# Board.net
KiCad netlist of a schematic drawn in EAGLE
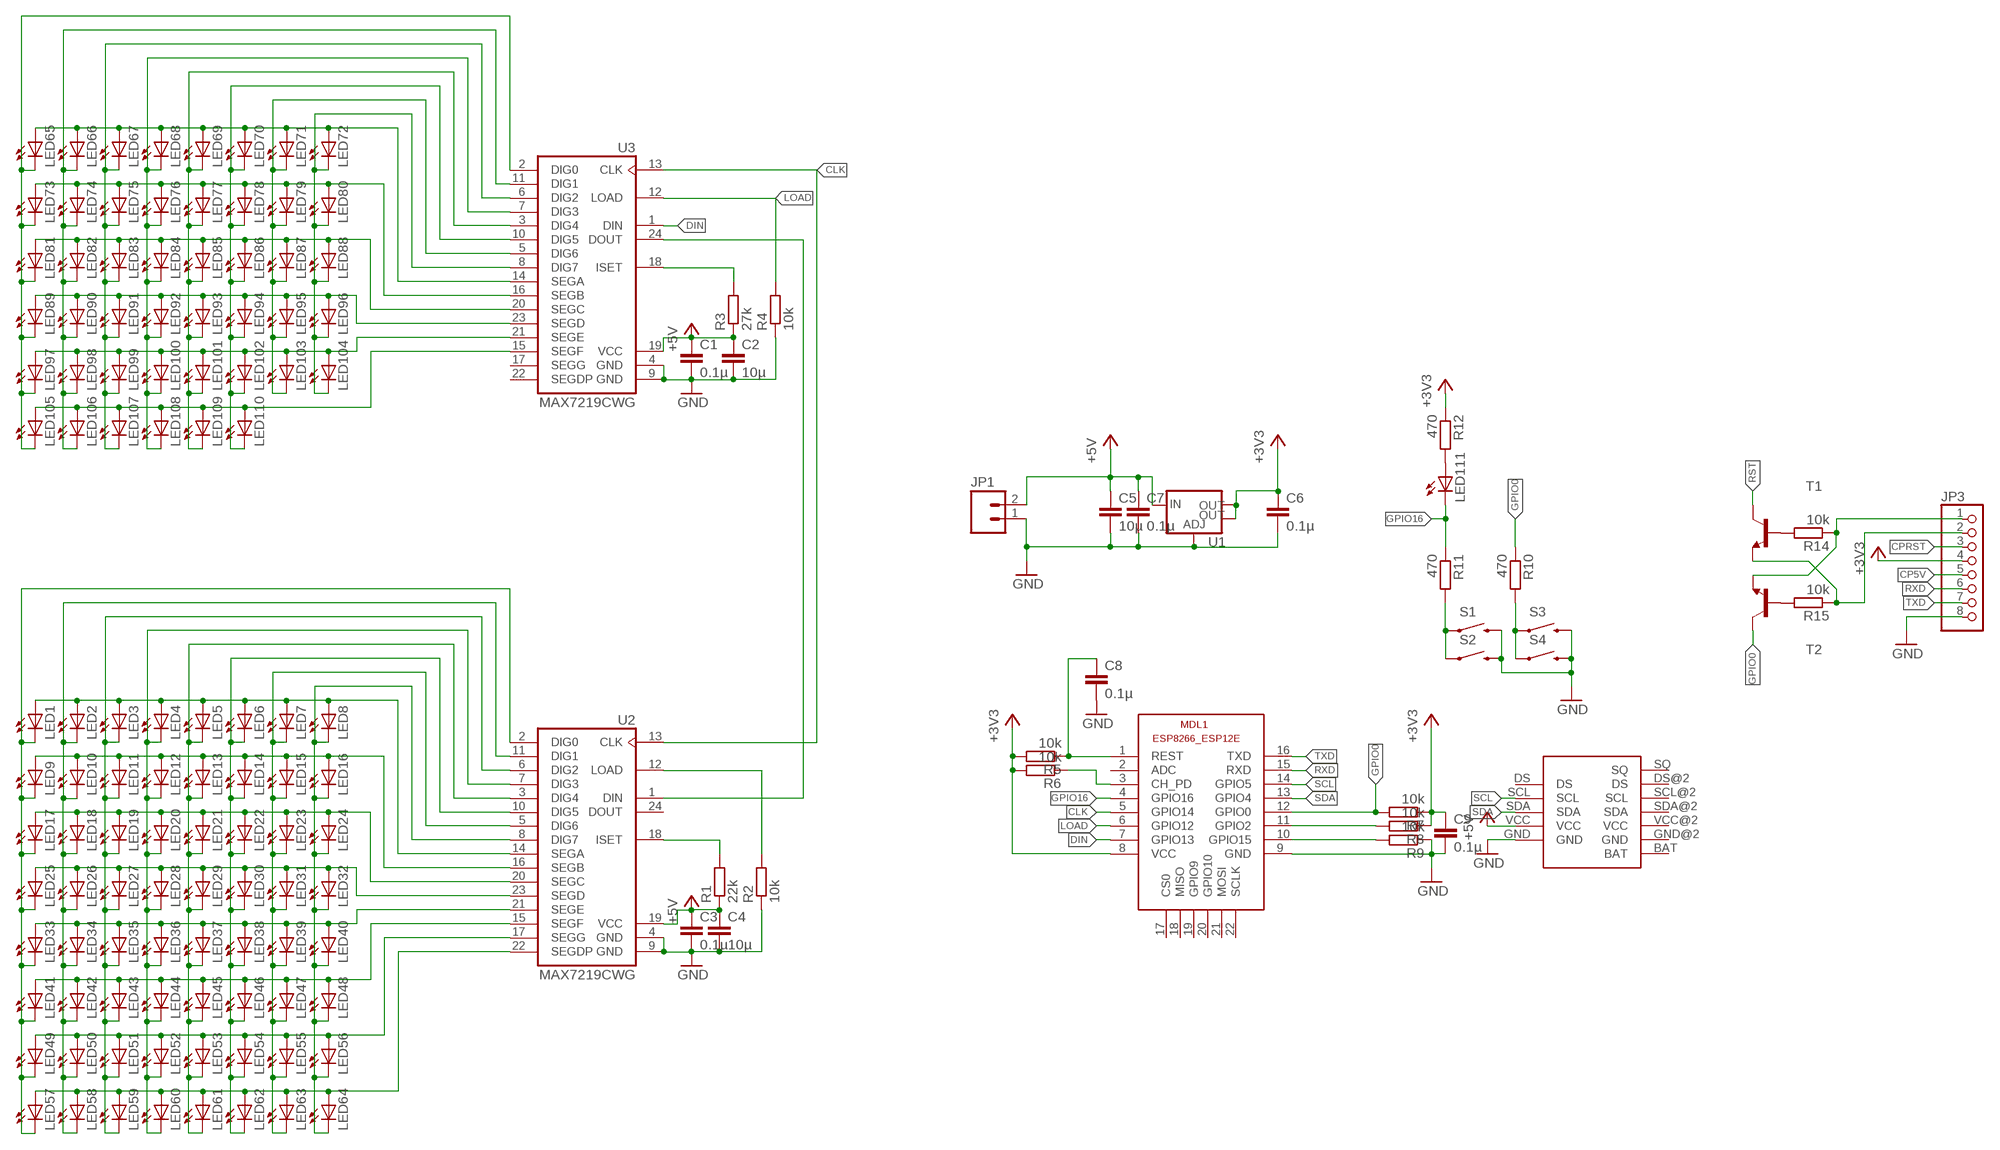
[diagram p0: schematic, sheet 1]

(export (version "E")
  (design (tool "Eeschema 10.0.6"))
  (components
    (comp (ref "C1")
      (value "0.1µ")
      (footprint "eagle-import:C0603")
      (libsource (lib "eagle-import") (part "C-EUC0603"))
    )
    (comp (ref "C2")
      (value "10µ")
      (footprint "eagle-import:C0603")
      (libsource (lib "eagle-import") (part "C-EUC0603"))
    )
    (comp (ref "C3")
      (value "0.1µ")
      (footprint "eagle-import:C0603")
      (libsource (lib "eagle-import") (part "C-EUC0603"))
    )
    (comp (ref "C4")
      (value "10µ")
      (footprint "eagle-import:C0603")
      (libsource (lib "eagle-import") (part "C-EUC0603"))
    )
    (comp (ref "C5")
      (value "10µ")
      (footprint "eagle-import:C0603")
      (libsource (lib "eagle-import") (part "C-EUC0603"))
    )
    (comp (ref "C6")
      (value "0.1µ")
      (footprint "eagle-import:C0603")
      (libsource (lib "eagle-import") (part "C-EUC0603"))
    )
    (comp (ref "C7")
      (value "0.1µ")
      (footprint "eagle-import:C0603")
      (libsource (lib "eagle-import") (part "C-EUC0603"))
    )
    (comp (ref "C8")
      (value "0.1µ")
      (footprint "eagle-import:C0603")
      (libsource (lib "eagle-import") (part "C-EUC0603"))
    )
    (comp (ref "C9")
      (value "0.1µ")
      (footprint "eagle-import:C0603")
      (libsource (lib "eagle-import") (part "C-EUC0603"))
    )
    (comp (ref "JP1")
      (value "M02POLAR")
      (footprint "eagle-import:MOLEX-1X2")
      (libsource (lib "eagle-import") (part "M02POLAR"))
    )
    (comp (ref "JP3")
      (value "PINHD-1X8")
      (footprint "eagle-import:1X08")
      (libsource (lib "eagle-import") (part "PINHD-1X8"))
    )
    (comp (ref "LED1")
      (value "LEDCHIPLED_0805")
      (footprint "eagle-import:CHIPLED_0805")
      (libsource (lib "eagle-import") (part "LEDCHIPLED_0805"))
    )
    (comp (ref "LED2")
      (value "LEDCHIPLED_0805")
      (footprint "eagle-import:CHIPLED_0805")
      (libsource (lib "eagle-import") (part "LEDCHIPLED_0805"))
    )
    (comp (ref "LED3")
      (value "LEDCHIPLED_0805")
      (footprint "eagle-import:CHIPLED_0805")
      (libsource (lib "eagle-import") (part "LEDCHIPLED_0805"))
    )
    (comp (ref "LED4")
      (value "LEDCHIPLED_0805")
      (footprint "eagle-import:CHIPLED_0805")
      (libsource (lib "eagle-import") (part "LEDCHIPLED_0805"))
    )
    (comp (ref "LED5")
      (value "LEDCHIPLED_0805")
      (footprint "eagle-import:CHIPLED_0805")
      (libsource (lib "eagle-import") (part "LEDCHIPLED_0805"))
    )
    (comp (ref "LED6")
      (value "LEDCHIPLED_0805")
      (footprint "eagle-import:CHIPLED_0805")
      (libsource (lib "eagle-import") (part "LEDCHIPLED_0805"))
    )
    (comp (ref "LED7")
      (value "LEDCHIPLED_0805")
      (footprint "eagle-import:CHIPLED_0805")
      (libsource (lib "eagle-import") (part "LEDCHIPLED_0805"))
    )
    (comp (ref "LED8")
      (value "LEDCHIPLED_0805")
      (footprint "eagle-import:CHIPLED_0805")
      (libsource (lib "eagle-import") (part "LEDCHIPLED_0805"))
    )
    (comp (ref "LED9")
      (value "LEDCHIPLED_0805")
      (footprint "eagle-import:CHIPLED_0805")
      (libsource (lib "eagle-import") (part "LEDCHIPLED_0805"))
    )
    (comp (ref "LED10")
      (value "LEDCHIPLED_0805")
      (footprint "eagle-import:CHIPLED_0805")
      (libsource (lib "eagle-import") (part "LEDCHIPLED_0805"))
    )
    (comp (ref "LED11")
      (value "LEDCHIPLED_0805")
      (footprint "eagle-import:CHIPLED_0805")
      (libsource (lib "eagle-import") (part "LEDCHIPLED_0805"))
    )
    (comp (ref "LED12")
      (value "LEDCHIPLED_0805")
      (footprint "eagle-import:CHIPLED_0805")
      (libsource (lib "eagle-import") (part "LEDCHIPLED_0805"))
    )
    (comp (ref "LED13")
      (value "LEDCHIPLED_0805")
      (footprint "eagle-import:CHIPLED_0805")
      (libsource (lib "eagle-import") (part "LEDCHIPLED_0805"))
    )
    (comp (ref "LED14")
      (value "LEDCHIPLED_0805")
      (footprint "eagle-import:CHIPLED_0805")
      (libsource (lib "eagle-import") (part "LEDCHIPLED_0805"))
    )
    (comp (ref "LED15")
      (value "LEDCHIPLED_0805")
      (footprint "eagle-import:CHIPLED_0805")
      (libsource (lib "eagle-import") (part "LEDCHIPLED_0805"))
    )
    (comp (ref "LED16")
      (value "LEDCHIPLED_0805")
      (footprint "eagle-import:CHIPLED_0805")
      (libsource (lib "eagle-import") (part "LEDCHIPLED_0805"))
    )
    (comp (ref "LED17")
      (value "LEDCHIPLED_0805")
      (footprint "eagle-import:CHIPLED_0805")
      (libsource (lib "eagle-import") (part "LEDCHIPLED_0805"))
    )
    (comp (ref "LED18")
      (value "LEDCHIPLED_0805")
      (footprint "eagle-import:CHIPLED_0805")
      (libsource (lib "eagle-import") (part "LEDCHIPLED_0805"))
    )
    (comp (ref "LED19")
      (value "LEDCHIPLED_0805")
      (footprint "eagle-import:CHIPLED_0805")
      (libsource (lib "eagle-import") (part "LEDCHIPLED_0805"))
    )
    (comp (ref "LED20")
      (value "LEDCHIPLED_0805")
      (footprint "eagle-import:CHIPLED_0805")
      (libsource (lib "eagle-import") (part "LEDCHIPLED_0805"))
    )
    (comp (ref "LED21")
      (value "LEDCHIPLED_0805")
      (footprint "eagle-import:CHIPLED_0805")
      (libsource (lib "eagle-import") (part "LEDCHIPLED_0805"))
    )
    (comp (ref "LED22")
      (value "LEDCHIPLED_0805")
      (footprint "eagle-import:CHIPLED_0805")
      (libsource (lib "eagle-import") (part "LEDCHIPLED_0805"))
    )
    (comp (ref "LED23")
      (value "LEDCHIPLED_0805")
      (footprint "eagle-import:CHIPLED_0805")
      (libsource (lib "eagle-import") (part "LEDCHIPLED_0805"))
    )
    (comp (ref "LED24")
      (value "LEDCHIPLED_0805")
      (footprint "eagle-import:CHIPLED_0805")
      (libsource (lib "eagle-import") (part "LEDCHIPLED_0805"))
    )
    (comp (ref "LED25")
      (value "LEDCHIPLED_0805")
      (footprint "eagle-import:CHIPLED_0805")
      (libsource (lib "eagle-import") (part "LEDCHIPLED_0805"))
    )
    (comp (ref "LED26")
      (value "LEDCHIPLED_0805")
      (footprint "eagle-import:CHIPLED_0805")
      (libsource (lib "eagle-import") (part "LEDCHIPLED_0805"))
    )
    (comp (ref "LED27")
      (value "LEDCHIPLED_0805")
      (footprint "eagle-import:CHIPLED_0805")
      (libsource (lib "eagle-import") (part "LEDCHIPLED_0805"))
    )
    (comp (ref "LED28")
      (value "LEDCHIPLED_0805")
      (footprint "eagle-import:CHIPLED_0805")
      (libsource (lib "eagle-import") (part "LEDCHIPLED_0805"))
    )
    (comp (ref "LED29")
      (value "LEDCHIPLED_0805")
      (footprint "eagle-import:CHIPLED_0805")
      (libsource (lib "eagle-import") (part "LEDCHIPLED_0805"))
    )
    (comp (ref "LED30")
      (value "LEDCHIPLED_0805")
      (footprint "eagle-import:CHIPLED_0805")
      (libsource (lib "eagle-import") (part "LEDCHIPLED_0805"))
    )
    (comp (ref "LED31")
      (value "LEDCHIPLED_0805")
      (footprint "eagle-import:CHIPLED_0805")
      (libsource (lib "eagle-import") (part "LEDCHIPLED_0805"))
    )
    (comp (ref "LED32")
      (value "LEDCHIPLED_0805")
      (footprint "eagle-import:CHIPLED_0805")
      (libsource (lib "eagle-import") (part "LEDCHIPLED_0805"))
    )
    (comp (ref "LED33")
      (value "LEDCHIPLED_0805")
      (footprint "eagle-import:CHIPLED_0805")
      (libsource (lib "eagle-import") (part "LEDCHIPLED_0805"))
    )
    (comp (ref "LED34")
      (value "LEDCHIPLED_0805")
      (footprint "eagle-import:CHIPLED_0805")
      (libsource (lib "eagle-import") (part "LEDCHIPLED_0805"))
    )
    (comp (ref "LED35")
      (value "LEDCHIPLED_0805")
      (footprint "eagle-import:CHIPLED_0805")
      (libsource (lib "eagle-import") (part "LEDCHIPLED_0805"))
    )
    (comp (ref "LED36")
      (value "LEDCHIPLED_0805")
      (footprint "eagle-import:CHIPLED_0805")
      (libsource (lib "eagle-import") (part "LEDCHIPLED_0805"))
    )
    (comp (ref "LED37")
      (value "LEDCHIPLED_0805")
      (footprint "eagle-import:CHIPLED_0805")
      (libsource (lib "eagle-import") (part "LEDCHIPLED_0805"))
    )
    (comp (ref "LED38")
      (value "LEDCHIPLED_0805")
      (footprint "eagle-import:CHIPLED_0805")
      (libsource (lib "eagle-import") (part "LEDCHIPLED_0805"))
    )
    (comp (ref "LED39")
      (value "LEDCHIPLED_0805")
      (footprint "eagle-import:CHIPLED_0805")
      (libsource (lib "eagle-import") (part "LEDCHIPLED_0805"))
    )
    (comp (ref "LED40")
      (value "LEDCHIPLED_0805")
      (footprint "eagle-import:CHIPLED_0805")
      (libsource (lib "eagle-import") (part "LEDCHIPLED_0805"))
    )
    (comp (ref "LED41")
      (value "LEDCHIPLED_0805")
      (footprint "eagle-import:CHIPLED_0805")
      (libsource (lib "eagle-import") (part "LEDCHIPLED_0805"))
    )
    (comp (ref "LED42")
      (value "LEDCHIPLED_0805")
      (footprint "eagle-import:CHIPLED_0805")
      (libsource (lib "eagle-import") (part "LEDCHIPLED_0805"))
    )
    (comp (ref "LED43")
      (value "LEDCHIPLED_0805")
      (footprint "eagle-import:CHIPLED_0805")
      (libsource (lib "eagle-import") (part "LEDCHIPLED_0805"))
    )
    (comp (ref "LED44")
      (value "LEDCHIPLED_0805")
      (footprint "eagle-import:CHIPLED_0805")
      (libsource (lib "eagle-import") (part "LEDCHIPLED_0805"))
    )
    (comp (ref "LED45")
      (value "LEDCHIPLED_0805")
      (footprint "eagle-import:CHIPLED_0805")
      (libsource (lib "eagle-import") (part "LEDCHIPLED_0805"))
    )
    (comp (ref "LED46")
      (value "LEDCHIPLED_0805")
      (footprint "eagle-import:CHIPLED_0805")
      (libsource (lib "eagle-import") (part "LEDCHIPLED_0805"))
    )
    (comp (ref "LED47")
      (value "LEDCHIPLED_0805")
      (footprint "eagle-import:CHIPLED_0805")
      (libsource (lib "eagle-import") (part "LEDCHIPLED_0805"))
    )
    (comp (ref "LED48")
      (value "LEDCHIPLED_0805")
      (footprint "eagle-import:CHIPLED_0805")
      (libsource (lib "eagle-import") (part "LEDCHIPLED_0805"))
    )
    (comp (ref "LED49")
      (value "LEDCHIPLED_0805")
      (footprint "eagle-import:CHIPLED_0805")
      (libsource (lib "eagle-import") (part "LEDCHIPLED_0805"))
    )
    (comp (ref "LED50")
      (value "LEDCHIPLED_0805")
      (footprint "eagle-import:CHIPLED_0805")
      (libsource (lib "eagle-import") (part "LEDCHIPLED_0805"))
    )
    (comp (ref "LED51")
      (value "LEDCHIPLED_0805")
      (footprint "eagle-import:CHIPLED_0805")
      (libsource (lib "eagle-import") (part "LEDCHIPLED_0805"))
    )
    (comp (ref "LED52")
      (value "LEDCHIPLED_0805")
      (footprint "eagle-import:CHIPLED_0805")
      (libsource (lib "eagle-import") (part "LEDCHIPLED_0805"))
    )
    (comp (ref "LED53")
      (value "LEDCHIPLED_0805")
      (footprint "eagle-import:CHIPLED_0805")
      (libsource (lib "eagle-import") (part "LEDCHIPLED_0805"))
    )
    (comp (ref "LED54")
      (value "LEDCHIPLED_0805")
      (footprint "eagle-import:CHIPLED_0805")
      (libsource (lib "eagle-import") (part "LEDCHIPLED_0805"))
    )
    (comp (ref "LED55")
      (value "LEDCHIPLED_0805")
      (footprint "eagle-import:CHIPLED_0805")
      (libsource (lib "eagle-import") (part "LEDCHIPLED_0805"))
    )
    (comp (ref "LED56")
      (value "LEDCHIPLED_0805")
      (footprint "eagle-import:CHIPLED_0805")
      (libsource (lib "eagle-import") (part "LEDCHIPLED_0805"))
    )
    (comp (ref "LED57")
      (value "LEDCHIPLED_0805")
      (footprint "eagle-import:CHIPLED_0805")
      (libsource (lib "eagle-import") (part "LEDCHIPLED_0805"))
    )
    (comp (ref "LED58")
      (value "LEDCHIPLED_0805")
      (footprint "eagle-import:CHIPLED_0805")
      (libsource (lib "eagle-import") (part "LEDCHIPLED_0805"))
    )
    (comp (ref "LED59")
      (value "LEDCHIPLED_0805")
      (footprint "eagle-import:CHIPLED_0805")
      (libsource (lib "eagle-import") (part "LEDCHIPLED_0805"))
    )
    (comp (ref "LED60")
      (value "LEDCHIPLED_0805")
      (footprint "eagle-import:CHIPLED_0805")
      (libsource (lib "eagle-import") (part "LEDCHIPLED_0805"))
    )
    (comp (ref "LED61")
      (value "LEDCHIPLED_0805")
      (footprint "eagle-import:CHIPLED_0805")
      (libsource (lib "eagle-import") (part "LEDCHIPLED_0805"))
    )
    (comp (ref "LED62")
      (value "LEDCHIPLED_0805")
      (footprint "eagle-import:CHIPLED_0805")
      (libsource (lib "eagle-import") (part "LEDCHIPLED_0805"))
    )
    (comp (ref "LED63")
      (value "LEDCHIPLED_0805")
      (footprint "eagle-import:CHIPLED_0805")
      (libsource (lib "eagle-import") (part "LEDCHIPLED_0805"))
    )
    (comp (ref "LED64")
      (value "LEDCHIPLED_0805")
      (footprint "eagle-import:CHIPLED_0805")
      (libsource (lib "eagle-import") (part "LEDCHIPLED_0805"))
    )
    (comp (ref "LED65")
      (value "LEDCHIPLED_0805")
      (footprint "eagle-import:CHIPLED_0805")
      (libsource (lib "eagle-import") (part "LEDCHIPLED_0805"))
    )
    (comp (ref "LED66")
      (value "LEDCHIPLED_0805")
      (footprint "eagle-import:CHIPLED_0805")
      (libsource (lib "eagle-import") (part "LEDCHIPLED_0805"))
    )
    (comp (ref "LED67")
      (value "LEDCHIPLED_0805")
      (footprint "eagle-import:CHIPLED_0805")
      (libsource (lib "eagle-import") (part "LEDCHIPLED_0805"))
    )
    (comp (ref "LED68")
      (value "LEDCHIPLED_0805")
      (footprint "eagle-import:CHIPLED_0805")
      (libsource (lib "eagle-import") (part "LEDCHIPLED_0805"))
    )
    (comp (ref "LED69")
      (value "LEDCHIPLED_0805")
      (footprint "eagle-import:CHIPLED_0805")
      (libsource (lib "eagle-import") (part "LEDCHIPLED_0805"))
    )
    (comp (ref "LED70")
      (value "LEDCHIPLED_0805")
      (footprint "eagle-import:CHIPLED_0805")
      (libsource (lib "eagle-import") (part "LEDCHIPLED_0805"))
    )
    (comp (ref "LED71")
      (value "LEDCHIPLED_0805")
      (footprint "eagle-import:CHIPLED_0805")
      (libsource (lib "eagle-import") (part "LEDCHIPLED_0805"))
    )
    (comp (ref "LED72")
      (value "LEDCHIPLED_0805")
      (footprint "eagle-import:CHIPLED_0805")
      (libsource (lib "eagle-import") (part "LEDCHIPLED_0805"))
    )
    (comp (ref "LED73")
      (value "LEDCHIPLED_0805")
      (footprint "eagle-import:CHIPLED_0805")
      (libsource (lib "eagle-import") (part "LEDCHIPLED_0805"))
    )
    (comp (ref "LED74")
      (value "LEDCHIPLED_0805")
      (footprint "eagle-import:CHIPLED_0805")
      (libsource (lib "eagle-import") (part "LEDCHIPLED_0805"))
    )
    (comp (ref "LED75")
      (value "LEDCHIPLED_0805")
      (footprint "eagle-import:CHIPLED_0805")
      (libsource (lib "eagle-import") (part "LEDCHIPLED_0805"))
    )
    (comp (ref "LED76")
      (value "LEDCHIPLED_0805")
      (footprint "eagle-import:CHIPLED_0805")
      (libsource (lib "eagle-import") (part "LEDCHIPLED_0805"))
    )
    (comp (ref "LED77")
      (value "LEDCHIPLED_0805")
      (footprint "eagle-import:CHIPLED_0805")
      (libsource (lib "eagle-import") (part "LEDCHIPLED_0805"))
    )
    (comp (ref "LED78")
      (value "LEDCHIPLED_0805")
      (footprint "eagle-import:CHIPLED_0805")
      (libsource (lib "eagle-import") (part "LEDCHIPLED_0805"))
    )
    (comp (ref "LED79")
      (value "LEDCHIPLED_0805")
      (footprint "eagle-import:CHIPLED_0805")
      (libsource (lib "eagle-import") (part "LEDCHIPLED_0805"))
    )
    (comp (ref "LED80")
      (value "LEDCHIPLED_0805")
      (footprint "eagle-import:CHIPLED_0805")
      (libsource (lib "eagle-import") (part "LEDCHIPLED_0805"))
    )
    (comp (ref "LED81")
      (value "LEDCHIPLED_0805")
      (footprint "eagle-import:CHIPLED_0805")
      (libsource (lib "eagle-import") (part "LEDCHIPLED_0805"))
    )
    (comp (ref "LED82")
      (value "LEDCHIPLED_0805")
      (footprint "eagle-import:CHIPLED_0805")
      (libsource (lib "eagle-import") (part "LEDCHIPLED_0805"))
    )
    (comp (ref "LED83")
      (value "LEDCHIPLED_0805")
      (footprint "eagle-import:CHIPLED_0805")
      (libsource (lib "eagle-import") (part "LEDCHIPLED_0805"))
    )
    (comp (ref "LED84")
      (value "LEDCHIPLED_0805")
      (footprint "eagle-import:CHIPLED_0805")
      (libsource (lib "eagle-import") (part "LEDCHIPLED_0805"))
    )
    (comp (ref "LED85")
      (value "LEDCHIPLED_0805")
      (footprint "eagle-import:CHIPLED_0805")
      (libsource (lib "eagle-import") (part "LEDCHIPLED_0805"))
    )
    (comp (ref "LED86")
      (value "LEDCHIPLED_0805")
      (footprint "eagle-import:CHIPLED_0805")
      (libsource (lib "eagle-import") (part "LEDCHIPLED_0805"))
    )
    (comp (ref "LED87")
      (value "LEDCHIPLED_0805")
      (footprint "eagle-import:CHIPLED_0805")
      (libsource (lib "eagle-import") (part "LEDCHIPLED_0805"))
    )
    (comp (ref "LED88")
      (value "LEDCHIPLED_0805")
      (footprint "eagle-import:CHIPLED_0805")
      (libsource (lib "eagle-import") (part "LEDCHIPLED_0805"))
    )
    (comp (ref "LED89")
      (value "LEDCHIPLED_0805")
      (footprint "eagle-import:CHIPLED_0805")
      (libsource (lib "eagle-import") (part "LEDCHIPLED_0805"))
    )
    (comp (ref "LED90")
      (value "LEDCHIPLED_0805")
      (footprint "eagle-import:CHIPLED_0805")
      (libsource (lib "eagle-import") (part "LEDCHIPLED_0805"))
    )
    (comp (ref "LED91")
      (value "LEDCHIPLED_0805")
      (footprint "eagle-import:CHIPLED_0805")
      (libsource (lib "eagle-import") (part "LEDCHIPLED_0805"))
    )
    (comp (ref "LED92")
      (value "LEDCHIPLED_0805")
      (footprint "eagle-import:CHIPLED_0805")
      (libsource (lib "eagle-import") (part "LEDCHIPLED_0805"))
    )
    (comp (ref "LED93")
      (value "LEDCHIPLED_0805")
      (footprint "eagle-import:CHIPLED_0805")
      (libsource (lib "eagle-import") (part "LEDCHIPLED_0805"))
    )
    (comp (ref "LED94")
      (value "LEDCHIPLED_0805")
      (footprint "eagle-import:CHIPLED_0805")
      (libsource (lib "eagle-import") (part "LEDCHIPLED_0805"))
    )
    (comp (ref "LED95")
      (value "LEDCHIPLED_0805")
      (footprint "eagle-import:CHIPLED_0805")
      (libsource (lib "eagle-import") (part "LEDCHIPLED_0805"))
    )
    (comp (ref "LED96")
      (value "LEDCHIPLED_0805")
      (footprint "eagle-import:CHIPLED_0805")
      (libsource (lib "eagle-import") (part "LEDCHIPLED_0805"))
    )
    (comp (ref "LED97")
      (value "LEDCHIPLED_0805")
      (footprint "eagle-import:CHIPLED_0805")
      (libsource (lib "eagle-import") (part "LEDCHIPLED_0805"))
    )
    (comp (ref "LED98")
      (value "LEDCHIPLED_0805")
      (footprint "eagle-import:CHIPLED_0805")
      (libsource (lib "eagle-import") (part "LEDCHIPLED_0805"))
    )
    (comp (ref "LED99")
      (value "LEDCHIPLED_0805")
      (footprint "eagle-import:CHIPLED_0805")
      (libsource (lib "eagle-import") (part "LEDCHIPLED_0805"))
    )
    (comp (ref "LED100")
      (value "LEDCHIPLED_0805")
      (footprint "eagle-import:CHIPLED_0805")
      (libsource (lib "eagle-import") (part "LEDCHIPLED_0805"))
    )
    (comp (ref "LED101")
      (value "LEDCHIPLED_0805")
      (footprint "eagle-import:CHIPLED_0805")
      (libsource (lib "eagle-import") (part "LEDCHIPLED_0805"))
    )
    (comp (ref "LED102")
      (value "LEDCHIPLED_0805")
      (footprint "eagle-import:CHIPLED_0805")
      (libsource (lib "eagle-import") (part "LEDCHIPLED_0805"))
    )
    (comp (ref "LED103")
      (value "LEDCHIPLED_0805")
      (footprint "eagle-import:CHIPLED_0805")
      (libsource (lib "eagle-import") (part "LEDCHIPLED_0805"))
    )
    (comp (ref "LED104")
      (value "LEDCHIPLED_0805")
      (footprint "eagle-import:CHIPLED_0805")
      (libsource (lib "eagle-import") (part "LEDCHIPLED_0805"))
    )
    (comp (ref "LED105")
      (value "LEDCHIPLED_0805")
      (footprint "eagle-import:CHIPLED_0805")
      (libsource (lib "eagle-import") (part "LEDCHIPLED_0805"))
    )
    (comp (ref "LED106")
      (value "LEDCHIPLED_0805")
      (footprint "eagle-import:CHIPLED_0805")
      (libsource (lib "eagle-import") (part "LEDCHIPLED_0805"))
    )
    (comp (ref "LED107")
      (value "LEDCHIPLED_0805")
      (footprint "eagle-import:CHIPLED_0805")
      (libsource (lib "eagle-import") (part "LEDCHIPLED_0805"))
    )
    (comp (ref "LED108")
      (value "LEDCHIPLED_0805")
      (footprint "eagle-import:CHIPLED_0805")
      (libsource (lib "eagle-import") (part "LEDCHIPLED_0805"))
    )
    (comp (ref "LED109")
      (value "LEDCHIPLED_0805")
      (footprint "eagle-import:CHIPLED_0805")
      (libsource (lib "eagle-import") (part "LEDCHIPLED_0805"))
    )
    (comp (ref "LED110")
      (value "LEDCHIPLED_0805")
      (footprint "eagle-import:CHIPLED_0805")
      (libsource (lib "eagle-import") (part "LEDCHIPLED_0805"))
    )
    (comp (ref "LED111")
      (value "LEDCHIPLED_0805")
      (footprint "eagle-import:CHIPLED_0805")
      (libsource (lib "eagle-import") (part "LEDCHIPLED_0805"))
    )
    (comp (ref "MDL1")
      (value "ESP8266-12EESP8266-ESP12E")
      (footprint "eagle-import:ESP8266-ESP12E")
      (libsource (lib "eagle-import") (part "ESP8266-12EESP8266-ESP12E"))
    )
    (comp (ref "R1")
      (value "22k")
      (footprint "eagle-import:R0603")
      (libsource (lib "eagle-import") (part "R-EU_R0603"))
    )
    (comp (ref "R2")
      (value "10k")
      (footprint "eagle-import:R0603")
      (libsource (lib "eagle-import") (part "R-EU_R0603"))
    )
    (comp (ref "R3")
      (value "27k")
      (footprint "eagle-import:R0603")
      (libsource (lib "eagle-import") (part "R-EU_R0603"))
    )
    (comp (ref "R4")
      (value "10k")
      (footprint "eagle-import:R0603")
      (libsource (lib "eagle-import") (part "R-EU_R0603"))
    )
    (comp (ref "R5")
      (value "10k")
      (footprint "eagle-import:R0603")
      (libsource (lib "eagle-import") (part "R-EU_R0603"))
    )
    (comp (ref "R6")
      (value "10k")
      (footprint "eagle-import:R0603")
      (libsource (lib "eagle-import") (part "R-EU_R0603"))
    )
    (comp (ref "R7")
      (value "10k")
      (footprint "eagle-import:R0603")
      (libsource (lib "eagle-import") (part "R-EU_R0603"))
    )
    (comp (ref "R8")
      (value "10k")
      (footprint "eagle-import:R0603")
      (libsource (lib "eagle-import") (part "R-EU_R0603"))
    )
    (comp (ref "R9")
      (value "10k")
      (footprint "eagle-import:R0603")
      (libsource (lib "eagle-import") (part "R-EU_R0603"))
    )
    (comp (ref "R10")
      (value "470")
      (footprint "eagle-import:R0603")
      (libsource (lib "eagle-import") (part "R-EU_R0603"))
    )
    (comp (ref "R11")
      (value "470")
      (footprint "eagle-import:R0603")
      (libsource (lib "eagle-import") (part "R-EU_R0603"))
    )
    (comp (ref "R12")
      (value "470")
      (footprint "eagle-import:R0603")
      (libsource (lib "eagle-import") (part "R-EU_R0603"))
    )
    (comp (ref "R14")
      (value "10k")
      (footprint "eagle-import:R0603")
      (libsource (lib "eagle-import") (part "R-EU_R0603"))
    )
    (comp (ref "R15")
      (value "10k")
      (footprint "eagle-import:R0603")
      (libsource (lib "eagle-import") (part "R-EU_R0603"))
    )
    (comp (ref "S1")
      (value "SWITCH-MOMENTARY-2SIDE_EZ")
      (footprint "eagle-import:TACTILE-PTH-SIDEEZ")
      (libsource (lib "eagle-import") (part "SWITCH-MOMENTARY-2SIDE_EZ"))
    )
    (comp (ref "S2")
      (value "SWITCH-MOMENTARY-2SMD-1101NE")
      (footprint "eagle-import:TACTILE-SWITCH-1101NE")
      (libsource (lib "eagle-import") (part "SWITCH-MOMENTARY-2SMD-1101NE"))
    )
    (comp (ref "S3")
      (value "SWITCH-MOMENTARY-2SIDE_EZ")
      (footprint "eagle-import:TACTILE-PTH-SIDEEZ")
      (libsource (lib "eagle-import") (part "SWITCH-MOMENTARY-2SIDE_EZ"))
    )
    (comp (ref "S4")
      (value "SWITCH-MOMENTARY-2SMD-1101NE")
      (footprint "eagle-import:TACTILE-SWITCH-1101NE")
      (libsource (lib "eagle-import") (part "SWITCH-MOMENTARY-2SMD-1101NE"))
    )
    (comp (ref "T1")
      (value "BC847-NPN-SOT23-BEC")
      (footprint "eagle-import:SOT23-BEC")
      (libsource (lib "eagle-import") (part "-NPN-SOT23-BECBC847"))
    )
    (comp (ref "T2")
      (value "BC847-NPN-SOT23-BEC")
      (footprint "eagle-import:SOT23-BEC")
      (libsource (lib "eagle-import") (part "-NPN-SOT23-BECBC847"))
    )
    (comp (ref "U$3")
      (value "DS1307-MODULE")
      (footprint "eagle-import:DS1307-MODULE")
      (libsource (lib "eagle-import") (part "DS1307-MODULE"))
    )
    (comp (ref "U1")
      (value "V_REG_LM1117SOT223")
      (footprint "eagle-import:SOT223")
      (libsource (lib "eagle-import") (part "V_REG_LM1117SOT223"))
    )
    (comp (ref "U2")
      (value "MAX7219CWG")
      (footprint "eagle-import:SO24L")
      (libsource (lib "eagle-import") (part "MAX7219CWG"))
    )
    (comp (ref "U3")
      (value "MAX7219CWG")
      (footprint "eagle-import:SO24L")
      (libsource (lib "eagle-import") (part "MAX7219CWG"))
    )
  )
  (nets
    (net (code "1") (name "+3V3") (class "Default")
      (node (ref "C6") (pin "1") (pinfunction "1_1") (pintype "passive"))
      (node (ref "C9") (pin "1") (pinfunction "1_1") (pintype "passive"))
      (node (ref "JP3") (pin "4") (pinfunction "4_4") (pintype "passive"))
      (node (ref "MDL1") (pin "8") (pinfunction "VCC_8") (pintype "bidirectional"))
      (node (ref "R12") (pin "1") (pinfunction "1_1") (pintype "passive"))
      (node (ref "R5") (pin "2") (pinfunction "2_2") (pintype "passive"))
      (node (ref "R6") (pin "2") (pinfunction "2_2") (pintype "passive"))
      (node (ref "R7") (pin "1") (pinfunction "1_1") (pintype "passive"))
      (node (ref "R8") (pin "1") (pinfunction "1_1") (pintype "passive"))
      (node (ref "U1") (pin "2") (pinfunction "OUT_2") (pintype "output"))
      (node (ref "U1") (pin "4") (pinfunction "OUT_4") (pintype "output"))
    )
    (net (code "2") (name "+5V") (class "Default")
      (node (ref "C1") (pin "1") (pinfunction "1_1") (pintype "passive"))
      (node (ref "C2") (pin "1") (pinfunction "1_1") (pintype "passive"))
      (node (ref "C3") (pin "1") (pinfunction "1_1") (pintype "passive"))
      (node (ref "C4") (pin "1") (pinfunction "1_1") (pintype "passive"))
      (node (ref "C5") (pin "1") (pinfunction "1_1") (pintype "passive"))
      (node (ref "C7") (pin "1") (pinfunction "1_1") (pintype "passive"))
      (node (ref "JP1") (pin "2") (pinfunction "2_2") (pintype "passive"))
      (node (ref "R1") (pin "1") (pinfunction "1_1") (pintype "passive"))
      (node (ref "R3") (pin "1") (pinfunction "1_1") (pintype "passive"))
      (node (ref "U$3") (pin "VCC") (pinfunction "VCC_VCC") (pintype "bidirectional"))
      (node (ref "U1") (pin "3") (pinfunction "IN_3") (pintype "input"))
      (node (ref "U2") (pin "19") (pinfunction "VCC_19") (pintype "power_in"))
      (node (ref "U3") (pin "19") (pinfunction "VCC_19") (pintype "power_in"))
    )
    (net (code "3") (name "CLK") (class "Default")
      (node (ref "MDL1") (pin "5") (pinfunction "GPIO14_5") (pintype "bidirectional"))
      (node (ref "U2") (pin "13") (pinfunction "CLK_13") (pintype "input"))
      (node (ref "U3") (pin "13") (pinfunction "CLK_13") (pintype "input"))
    )
    (net (code "4") (name "CP5V") (class "Default")
      (node (ref "JP3") (pin "5") (pinfunction "5_5") (pintype "passive"))
    )
    (net (code "5") (name "CPRST") (class "Default")
      (node (ref "JP3") (pin "3") (pinfunction "3_3") (pintype "passive"))
    )
    (net (code "6") (name "DIN") (class "Default")
      (node (ref "MDL1") (pin "7") (pinfunction "GPIO13_7") (pintype "bidirectional"))
      (node (ref "U3") (pin "1") (pinfunction "DIN_1") (pintype "input"))
    )
    (net (code "7") (name "GND") (class "Default")
      (node (ref "C1") (pin "2") (pinfunction "2_2") (pintype "passive"))
      (node (ref "C2") (pin "2") (pinfunction "2_2") (pintype "passive"))
      (node (ref "C3") (pin "2") (pinfunction "2_2") (pintype "passive"))
      (node (ref "C4") (pin "2") (pinfunction "2_2") (pintype "passive"))
      (node (ref "C5") (pin "2") (pinfunction "2_2") (pintype "passive"))
      (node (ref "C6") (pin "2") (pinfunction "2_2") (pintype "passive"))
      (node (ref "C7") (pin "2") (pinfunction "2_2") (pintype "passive"))
      (node (ref "C8") (pin "2") (pinfunction "2_2") (pintype "passive"))
      (node (ref "C9") (pin "2") (pinfunction "2_2") (pintype "passive"))
      (node (ref "JP1") (pin "1") (pinfunction "1_1") (pintype "passive"))
      (node (ref "JP3") (pin "8") (pinfunction "8_8") (pintype "passive"))
      (node (ref "MDL1") (pin "9") (pinfunction "GND_9") (pintype "bidirectional"))
      (node (ref "R2") (pin "1") (pinfunction "1_1") (pintype "passive"))
      (node (ref "R4") (pin "1") (pinfunction "1_1") (pintype "passive"))
      (node (ref "R9") (pin "1") (pinfunction "1_1") (pintype "passive"))
      (node (ref "S1") (pin "2") (pinfunction "2_2") (pintype "passive"))
      (node (ref "S2") (pin "2") (pinfunction "2_2") (pintype "passive"))
      (node (ref "S3") (pin "2") (pinfunction "2_2") (pintype "passive"))
      (node (ref "S4") (pin "2") (pinfunction "2_2") (pintype "passive"))
      (node (ref "U$3") (pin "GND") (pinfunction "GND_GND") (pintype "bidirectional"))
      (node (ref "U1") (pin "1") (pinfunction "ADJ_1") (pintype "input"))
      (node (ref "U2") (pin "4") (pinfunction "GND_4") (pintype "power_in"))
      (node (ref "U2") (pin "9") (pinfunction "GND_9") (pintype "power_in"))
      (node (ref "U3") (pin "4") (pinfunction "GND_4") (pintype "power_in"))
      (node (ref "U3") (pin "9") (pinfunction "GND_9") (pintype "power_in"))
    )
    (net (code "8") (name "GPIO0") (class "Default")
      (node (ref "MDL1") (pin "12") (pinfunction "GPIO0_12") (pintype "bidirectional"))
      (node (ref "R10") (pin "1") (pinfunction "1_1") (pintype "passive"))
      (node (ref "R7") (pin "2") (pinfunction "2_2") (pintype "passive"))
      (node (ref "T2") (pin "C") (pinfunction "C_C") (pintype "passive"))
    )
    (net (code "9") (name "GPIO16") (class "Default")
      (node (ref "LED111") (pin "C") (pinfunction "C_C") (pintype "passive"))
      (node (ref "MDL1") (pin "4") (pinfunction "GPIO16_4") (pintype "bidirectional"))
      (node (ref "R11") (pin "1") (pinfunction "1_1") (pintype "passive"))
    )
    (net (code "10") (name "LOAD") (class "Default")
      (node (ref "MDL1") (pin "6") (pinfunction "GPIO12_6") (pintype "bidirectional"))
      (node (ref "R4") (pin "2") (pinfunction "2_2") (pintype "passive"))
      (node (ref "U3") (pin "12") (pinfunction "LOAD_12") (pintype "input"))
    )
    (net (code "11") (name "Net-(JP3-Pad1)") (class "Default")
      (node (ref "JP3") (pin "1") (pinfunction "1_1") (pintype "passive"))
      (node (ref "R14") (pin "1") (pinfunction "1_1") (pintype "passive"))
      (node (ref "T2") (pin "E") (pinfunction "E_E") (pintype "passive"))
    )
    (net (code "12") (name "Net-(JP3-Pad2)") (class "Default")
      (node (ref "JP3") (pin "2") (pinfunction "2_2") (pintype "passive"))
      (node (ref "R15") (pin "1") (pinfunction "1_1") (pintype "passive"))
      (node (ref "T1") (pin "E") (pinfunction "E_E") (pintype "passive"))
    )
    (net (code "13") (name "Net-(LED111-PadA)") (class "Default")
      (node (ref "LED111") (pin "A") (pinfunction "A_A") (pintype "passive"))
      (node (ref "R12") (pin "2") (pinfunction "2_2") (pintype "passive"))
    )
    (net (code "14") (name "Net-(MDL1-CH_PD)") (class "Default")
      (node (ref "MDL1") (pin "3") (pinfunction "CH_PD_3") (pintype "bidirectional"))
      (node (ref "R6") (pin "1") (pinfunction "1_1") (pintype "passive"))
    )
    (net (code "15") (name "Net-(MDL1-GPIO2)") (class "Default")
      (node (ref "MDL1") (pin "11") (pinfunction "GPIO2_11") (pintype "bidirectional"))
      (node (ref "R8") (pin "2") (pinfunction "2_2") (pintype "passive"))
    )
    (net (code "16") (name "Net-(MDL1-GPIO15)") (class "Default")
      (node (ref "MDL1") (pin "10") (pinfunction "GPIO15_10") (pintype "bidirectional"))
      (node (ref "R9") (pin "2") (pinfunction "2_2") (pintype "passive"))
    )
    (net (code "17") (name "Net-(R10-Pad2)") (class "Default")
      (node (ref "R10") (pin "2") (pinfunction "2_2") (pintype "passive"))
      (node (ref "S3") (pin "1") (pinfunction "1_1") (pintype "passive"))
      (node (ref "S4") (pin "1") (pinfunction "1_1") (pintype "passive"))
    )
    (net (code "18") (name "Net-(R11-Pad2)") (class "Default")
      (node (ref "R11") (pin "2") (pinfunction "2_2") (pintype "passive"))
      (node (ref "S1") (pin "1") (pinfunction "1_1") (pintype "passive"))
      (node (ref "S2") (pin "1") (pinfunction "1_1") (pintype "passive"))
    )
    (net (code "19") (name "Net-(R14-Pad2)") (class "Default")
      (node (ref "R14") (pin "2") (pinfunction "2_2") (pintype "passive"))
      (node (ref "T1") (pin "B") (pinfunction "B_B") (pintype "passive"))
    )
    (net (code "20") (name "Net-(R15-Pad2)") (class "Default")
      (node (ref "R15") (pin "2") (pinfunction "2_2") (pintype "passive"))
      (node (ref "T2") (pin "B") (pinfunction "B_B") (pintype "passive"))
    )
    (net (code "21") (name "Net-(U2-DIG0)") (class "Default")
      (node (ref "LED1") (pin "C") (pinfunction "C_C") (pintype "passive"))
      (node (ref "LED17") (pin "C") (pinfunction "C_C") (pintype "passive"))
      (node (ref "LED25") (pin "C") (pinfunction "C_C") (pintype "passive"))
      (node (ref "LED33") (pin "C") (pinfunction "C_C") (pintype "passive"))
      (node (ref "LED41") (pin "C") (pinfunction "C_C") (pintype "passive"))
      (node (ref "LED49") (pin "C") (pinfunction "C_C") (pintype "passive"))
      (node (ref "LED57") (pin "C") (pinfunction "C_C") (pintype "passive"))
      (node (ref "LED9") (pin "C") (pinfunction "C_C") (pintype "passive"))
      (node (ref "U2") (pin "2") (pinfunction "DIG0_2") (pintype "output"))
    )
    (net (code "22") (name "Net-(U2-DIG1)") (class "Default")
      (node (ref "LED10") (pin "C") (pinfunction "C_C") (pintype "passive"))
      (node (ref "LED18") (pin "C") (pinfunction "C_C") (pintype "passive"))
      (node (ref "LED2") (pin "C") (pinfunction "C_C") (pintype "passive"))
      (node (ref "LED26") (pin "C") (pinfunction "C_C") (pintype "passive"))
      (node (ref "LED34") (pin "C") (pinfunction "C_C") (pintype "passive"))
      (node (ref "LED42") (pin "C") (pinfunction "C_C") (pintype "passive"))
      (node (ref "LED50") (pin "C") (pinfunction "C_C") (pintype "passive"))
      (node (ref "LED58") (pin "C") (pinfunction "C_C") (pintype "passive"))
      (node (ref "U2") (pin "11") (pinfunction "DIG1_11") (pintype "output"))
    )
    (net (code "23") (name "Net-(U2-DIG2)") (class "Default")
      (node (ref "LED11") (pin "C") (pinfunction "C_C") (pintype "passive"))
      (node (ref "LED19") (pin "C") (pinfunction "C_C") (pintype "passive"))
      (node (ref "LED27") (pin "C") (pinfunction "C_C") (pintype "passive"))
      (node (ref "LED3") (pin "C") (pinfunction "C_C") (pintype "passive"))
      (node (ref "LED35") (pin "C") (pinfunction "C_C") (pintype "passive"))
      (node (ref "LED43") (pin "C") (pinfunction "C_C") (pintype "passive"))
      (node (ref "LED51") (pin "C") (pinfunction "C_C") (pintype "passive"))
      (node (ref "LED59") (pin "C") (pinfunction "C_C") (pintype "passive"))
      (node (ref "U2") (pin "6") (pinfunction "DIG2_6") (pintype "output"))
    )
    (net (code "24") (name "Net-(U2-DIG3)") (class "Default")
      (node (ref "LED12") (pin "C") (pinfunction "C_C") (pintype "passive"))
      (node (ref "LED20") (pin "C") (pinfunction "C_C") (pintype "passive"))
      (node (ref "LED28") (pin "C") (pinfunction "C_C") (pintype "passive"))
      (node (ref "LED36") (pin "C") (pinfunction "C_C") (pintype "passive"))
      (node (ref "LED4") (pin "C") (pinfunction "C_C") (pintype "passive"))
      (node (ref "LED44") (pin "C") (pinfunction "C_C") (pintype "passive"))
      (node (ref "LED52") (pin "C") (pinfunction "C_C") (pintype "passive"))
      (node (ref "LED60") (pin "C") (pinfunction "C_C") (pintype "passive"))
      (node (ref "U2") (pin "7") (pinfunction "DIG3_7") (pintype "output"))
    )
    (net (code "25") (name "Net-(U2-DIG4)") (class "Default")
      (node (ref "LED13") (pin "C") (pinfunction "C_C") (pintype "passive"))
      (node (ref "LED21") (pin "C") (pinfunction "C_C") (pintype "passive"))
      (node (ref "LED29") (pin "C") (pinfunction "C_C") (pintype "passive"))
      (node (ref "LED37") (pin "C") (pinfunction "C_C") (pintype "passive"))
      (node (ref "LED45") (pin "C") (pinfunction "C_C") (pintype "passive"))
      (node (ref "LED5") (pin "C") (pinfunction "C_C") (pintype "passive"))
      (node (ref "LED53") (pin "C") (pinfunction "C_C") (pintype "passive"))
      (node (ref "LED61") (pin "C") (pinfunction "C_C") (pintype "passive"))
      (node (ref "U2") (pin "3") (pinfunction "DIG4_3") (pintype "output"))
    )
    (net (code "26") (name "Net-(U2-DIG5)") (class "Default")
      (node (ref "LED14") (pin "C") (pinfunction "C_C") (pintype "passive"))
      (node (ref "LED22") (pin "C") (pinfunction "C_C") (pintype "passive"))
      (node (ref "LED30") (pin "C") (pinfunction "C_C") (pintype "passive"))
      (node (ref "LED38") (pin "C") (pinfunction "C_C") (pintype "passive"))
      (node (ref "LED46") (pin "C") (pinfunction "C_C") (pintype "passive"))
      (node (ref "LED54") (pin "C") (pinfunction "C_C") (pintype "passive"))
      (node (ref "LED6") (pin "C") (pinfunction "C_C") (pintype "passive"))
      (node (ref "LED62") (pin "C") (pinfunction "C_C") (pintype "passive"))
      (node (ref "U2") (pin "10") (pinfunction "DIG5_10") (pintype "output"))
    )
    (net (code "27") (name "Net-(U2-DIG6)") (class "Default")
      (node (ref "LED15") (pin "C") (pinfunction "C_C") (pintype "passive"))
      (node (ref "LED23") (pin "C") (pinfunction "C_C") (pintype "passive"))
      (node (ref "LED31") (pin "C") (pinfunction "C_C") (pintype "passive"))
      (node (ref "LED39") (pin "C") (pinfunction "C_C") (pintype "passive"))
      (node (ref "LED47") (pin "C") (pinfunction "C_C") (pintype "passive"))
      (node (ref "LED55") (pin "C") (pinfunction "C_C") (pintype "passive"))
      (node (ref "LED63") (pin "C") (pinfunction "C_C") (pintype "passive"))
      (node (ref "LED7") (pin "C") (pinfunction "C_C") (pintype "passive"))
      (node (ref "U2") (pin "5") (pinfunction "DIG6_5") (pintype "output"))
    )
    (net (code "28") (name "Net-(U2-DIG7)") (class "Default")
      (node (ref "LED16") (pin "C") (pinfunction "C_C") (pintype "passive"))
      (node (ref "LED24") (pin "C") (pinfunction "C_C") (pintype "passive"))
      (node (ref "LED32") (pin "C") (pinfunction "C_C") (pintype "passive"))
      (node (ref "LED40") (pin "C") (pinfunction "C_C") (pintype "passive"))
      (node (ref "LED48") (pin "C") (pinfunction "C_C") (pintype "passive"))
      (node (ref "LED56") (pin "C") (pinfunction "C_C") (pintype "passive"))
      (node (ref "LED64") (pin "C") (pinfunction "C_C") (pintype "passive"))
      (node (ref "LED8") (pin "C") (pinfunction "C_C") (pintype "passive"))
      (node (ref "U2") (pin "8") (pinfunction "DIG7_8") (pintype "output"))
    )
    (net (code "29") (name "Net-(U2-DIN)") (class "Default")
      (node (ref "U2") (pin "1") (pinfunction "DIN_1") (pintype "input"))
      (node (ref "U3") (pin "24") (pinfunction "DOUT_24") (pintype "output"))
    )
    (net (code "30") (name "Net-(U2-ISET)") (class "Default")
      (node (ref "R1") (pin "2") (pinfunction "2_2") (pintype "passive"))
      (node (ref "U2") (pin "18") (pinfunction "ISET_18") (pintype "input"))
    )
    (net (code "31") (name "Net-(U2-LOAD)") (class "Default")
      (node (ref "R2") (pin "2") (pinfunction "2_2") (pintype "passive"))
      (node (ref "U2") (pin "12") (pinfunction "LOAD_12") (pintype "input"))
    )
    (net (code "32") (name "Net-(U2-SEGA)") (class "Default")
      (node (ref "LED1") (pin "A") (pinfunction "A_A") (pintype "passive"))
      (node (ref "LED2") (pin "A") (pinfunction "A_A") (pintype "passive"))
      (node (ref "LED3") (pin "A") (pinfunction "A_A") (pintype "passive"))
      (node (ref "LED4") (pin "A") (pinfunction "A_A") (pintype "passive"))
      (node (ref "LED5") (pin "A") (pinfunction "A_A") (pintype "passive"))
      (node (ref "LED6") (pin "A") (pinfunction "A_A") (pintype "passive"))
      (node (ref "LED7") (pin "A") (pinfunction "A_A") (pintype "passive"))
      (node (ref "LED8") (pin "A") (pinfunction "A_A") (pintype "passive"))
      (node (ref "U2") (pin "14") (pinfunction "SEGA_14") (pintype "output"))
    )
    (net (code "33") (name "Net-(U2-SEGB)") (class "Default")
      (node (ref "LED10") (pin "A") (pinfunction "A_A") (pintype "passive"))
      (node (ref "LED11") (pin "A") (pinfunction "A_A") (pintype "passive"))
      (node (ref "LED12") (pin "A") (pinfunction "A_A") (pintype "passive"))
      (node (ref "LED13") (pin "A") (pinfunction "A_A") (pintype "passive"))
      (node (ref "LED14") (pin "A") (pinfunction "A_A") (pintype "passive"))
      (node (ref "LED15") (pin "A") (pinfunction "A_A") (pintype "passive"))
      (node (ref "LED16") (pin "A") (pinfunction "A_A") (pintype "passive"))
      (node (ref "LED9") (pin "A") (pinfunction "A_A") (pintype "passive"))
      (node (ref "U2") (pin "16") (pinfunction "SEGB_16") (pintype "output"))
    )
    (net (code "34") (name "Net-(U2-SEGC)") (class "Default")
      (node (ref "LED17") (pin "A") (pinfunction "A_A") (pintype "passive"))
      (node (ref "LED18") (pin "A") (pinfunction "A_A") (pintype "passive"))
      (node (ref "LED19") (pin "A") (pinfunction "A_A") (pintype "passive"))
      (node (ref "LED20") (pin "A") (pinfunction "A_A") (pintype "passive"))
      (node (ref "LED21") (pin "A") (pinfunction "A_A") (pintype "passive"))
      (node (ref "LED22") (pin "A") (pinfunction "A_A") (pintype "passive"))
      (node (ref "LED23") (pin "A") (pinfunction "A_A") (pintype "passive"))
      (node (ref "LED24") (pin "A") (pinfunction "A_A") (pintype "passive"))
      (node (ref "U2") (pin "20") (pinfunction "SEGC_20") (pintype "output"))
    )
    (net (code "35") (name "Net-(U2-SEGD)") (class "Default")
      (node (ref "LED25") (pin "A") (pinfunction "A_A") (pintype "passive"))
      (node (ref "LED26") (pin "A") (pinfunction "A_A") (pintype "passive"))
      (node (ref "LED27") (pin "A") (pinfunction "A_A") (pintype "passive"))
      (node (ref "LED28") (pin "A") (pinfunction "A_A") (pintype "passive"))
      (node (ref "LED29") (pin "A") (pinfunction "A_A") (pintype "passive"))
      (node (ref "LED30") (pin "A") (pinfunction "A_A") (pintype "passive"))
      (node (ref "LED31") (pin "A") (pinfunction "A_A") (pintype "passive"))
      (node (ref "LED32") (pin "A") (pinfunction "A_A") (pintype "passive"))
      (node (ref "U2") (pin "23") (pinfunction "SEGD_23") (pintype "output"))
    )
    (net (code "36") (name "Net-(U2-SEGDP)") (class "Default")
      (node (ref "LED57") (pin "A") (pinfunction "A_A") (pintype "passive"))
      (node (ref "LED58") (pin "A") (pinfunction "A_A") (pintype "passive"))
      (node (ref "LED59") (pin "A") (pinfunction "A_A") (pintype "passive"))
      (node (ref "LED60") (pin "A") (pinfunction "A_A") (pintype "passive"))
      (node (ref "LED61") (pin "A") (pinfunction "A_A") (pintype "passive"))
      (node (ref "LED62") (pin "A") (pinfunction "A_A") (pintype "passive"))
      (node (ref "LED63") (pin "A") (pinfunction "A_A") (pintype "passive"))
      (node (ref "LED64") (pin "A") (pinfunction "A_A") (pintype "passive"))
      (node (ref "U2") (pin "22") (pinfunction "SEGDP_22") (pintype "output"))
    )
    (net (code "37") (name "Net-(U2-SEGE)") (class "Default")
      (node (ref "LED33") (pin "A") (pinfunction "A_A") (pintype "passive"))
      (node (ref "LED34") (pin "A") (pinfunction "A_A") (pintype "passive"))
      (node (ref "LED35") (pin "A") (pinfunction "A_A") (pintype "passive"))
      (node (ref "LED36") (pin "A") (pinfunction "A_A") (pintype "passive"))
      (node (ref "LED37") (pin "A") (pinfunction "A_A") (pintype "passive"))
      (node (ref "LED38") (pin "A") (pinfunction "A_A") (pintype "passive"))
      (node (ref "LED39") (pin "A") (pinfunction "A_A") (pintype "passive"))
      (node (ref "LED40") (pin "A") (pinfunction "A_A") (pintype "passive"))
      (node (ref "U2") (pin "21") (pinfunction "SEGE_21") (pintype "output"))
    )
    (net (code "38") (name "Net-(U2-SEGF)") (class "Default")
      (node (ref "LED41") (pin "A") (pinfunction "A_A") (pintype "passive"))
      (node (ref "LED42") (pin "A") (pinfunction "A_A") (pintype "passive"))
      (node (ref "LED43") (pin "A") (pinfunction "A_A") (pintype "passive"))
      (node (ref "LED44") (pin "A") (pinfunction "A_A") (pintype "passive"))
      (node (ref "LED45") (pin "A") (pinfunction "A_A") (pintype "passive"))
      (node (ref "LED46") (pin "A") (pinfunction "A_A") (pintype "passive"))
      (node (ref "LED47") (pin "A") (pinfunction "A_A") (pintype "passive"))
      (node (ref "LED48") (pin "A") (pinfunction "A_A") (pintype "passive"))
      (node (ref "U2") (pin "15") (pinfunction "SEGF_15") (pintype "output"))
    )
    (net (code "39") (name "Net-(U2-SEGG)") (class "Default")
      (node (ref "LED49") (pin "A") (pinfunction "A_A") (pintype "passive"))
      (node (ref "LED50") (pin "A") (pinfunction "A_A") (pintype "passive"))
      (node (ref "LED51") (pin "A") (pinfunction "A_A") (pintype "passive"))
      (node (ref "LED52") (pin "A") (pinfunction "A_A") (pintype "passive"))
      (node (ref "LED53") (pin "A") (pinfunction "A_A") (pintype "passive"))
      (node (ref "LED54") (pin "A") (pinfunction "A_A") (pintype "passive"))
      (node (ref "LED55") (pin "A") (pinfunction "A_A") (pintype "passive"))
      (node (ref "LED56") (pin "A") (pinfunction "A_A") (pintype "passive"))
      (node (ref "U2") (pin "17") (pinfunction "SEGG_17") (pintype "output"))
    )
    (net (code "40") (name "Net-(U3-DIG0)") (class "Default")
      (node (ref "LED105") (pin "C") (pinfunction "C_C") (pintype "passive"))
      (node (ref "LED65") (pin "C") (pinfunction "C_C") (pintype "passive"))
      (node (ref "LED73") (pin "C") (pinfunction "C_C") (pintype "passive"))
      (node (ref "LED81") (pin "C") (pinfunction "C_C") (pintype "passive"))
      (node (ref "LED89") (pin "C") (pinfunction "C_C") (pintype "passive"))
      (node (ref "LED97") (pin "C") (pinfunction "C_C") (pintype "passive"))
      (node (ref "U3") (pin "2") (pinfunction "DIG0_2") (pintype "output"))
    )
    (net (code "41") (name "Net-(U3-DIG1)") (class "Default")
      (node (ref "LED106") (pin "C") (pinfunction "C_C") (pintype "passive"))
      (node (ref "LED66") (pin "C") (pinfunction "C_C") (pintype "passive"))
      (node (ref "LED74") (pin "C") (pinfunction "C_C") (pintype "passive"))
      (node (ref "LED82") (pin "C") (pinfunction "C_C") (pintype "passive"))
      (node (ref "LED90") (pin "C") (pinfunction "C_C") (pintype "passive"))
      (node (ref "LED98") (pin "C") (pinfunction "C_C") (pintype "passive"))
      (node (ref "U3") (pin "11") (pinfunction "DIG1_11") (pintype "output"))
    )
    (net (code "42") (name "Net-(U3-DIG2)") (class "Default")
      (node (ref "LED107") (pin "C") (pinfunction "C_C") (pintype "passive"))
      (node (ref "LED67") (pin "C") (pinfunction "C_C") (pintype "passive"))
      (node (ref "LED75") (pin "C") (pinfunction "C_C") (pintype "passive"))
      (node (ref "LED83") (pin "C") (pinfunction "C_C") (pintype "passive"))
      (node (ref "LED91") (pin "C") (pinfunction "C_C") (pintype "passive"))
      (node (ref "LED99") (pin "C") (pinfunction "C_C") (pintype "passive"))
      (node (ref "U3") (pin "6") (pinfunction "DIG2_6") (pintype "output"))
    )
    (net (code "43") (name "Net-(U3-DIG3)") (class "Default")
      (node (ref "LED100") (pin "C") (pinfunction "C_C") (pintype "passive"))
      (node (ref "LED108") (pin "C") (pinfunction "C_C") (pintype "passive"))
      (node (ref "LED68") (pin "C") (pinfunction "C_C") (pintype "passive"))
      (node (ref "LED76") (pin "C") (pinfunction "C_C") (pintype "passive"))
      (node (ref "LED84") (pin "C") (pinfunction "C_C") (pintype "passive"))
      (node (ref "LED92") (pin "C") (pinfunction "C_C") (pintype "passive"))
      (node (ref "U3") (pin "7") (pinfunction "DIG3_7") (pintype "output"))
    )
    (net (code "44") (name "Net-(U3-DIG4)") (class "Default")
      (node (ref "LED101") (pin "C") (pinfunction "C_C") (pintype "passive"))
      (node (ref "LED109") (pin "C") (pinfunction "C_C") (pintype "passive"))
      (node (ref "LED69") (pin "C") (pinfunction "C_C") (pintype "passive"))
      (node (ref "LED77") (pin "C") (pinfunction "C_C") (pintype "passive"))
      (node (ref "LED85") (pin "C") (pinfunction "C_C") (pintype "passive"))
      (node (ref "LED93") (pin "C") (pinfunction "C_C") (pintype "passive"))
      (node (ref "U3") (pin "3") (pinfunction "DIG4_3") (pintype "output"))
    )
    (net (code "45") (name "Net-(U3-DIG5)") (class "Default")
      (node (ref "LED102") (pin "C") (pinfunction "C_C") (pintype "passive"))
      (node (ref "LED110") (pin "C") (pinfunction "C_C") (pintype "passive"))
      (node (ref "LED70") (pin "C") (pinfunction "C_C") (pintype "passive"))
      (node (ref "LED78") (pin "C") (pinfunction "C_C") (pintype "passive"))
      (node (ref "LED86") (pin "C") (pinfunction "C_C") (pintype "passive"))
      (node (ref "LED94") (pin "C") (pinfunction "C_C") (pintype "passive"))
      (node (ref "U3") (pin "10") (pinfunction "DIG5_10") (pintype "output"))
    )
    (net (code "46") (name "Net-(U3-DIG6)") (class "Default")
      (node (ref "LED103") (pin "C") (pinfunction "C_C") (pintype "passive"))
      (node (ref "LED71") (pin "C") (pinfunction "C_C") (pintype "passive"))
      (node (ref "LED79") (pin "C") (pinfunction "C_C") (pintype "passive"))
      (node (ref "LED87") (pin "C") (pinfunction "C_C") (pintype "passive"))
      (node (ref "LED95") (pin "C") (pinfunction "C_C") (pintype "passive"))
      (node (ref "U3") (pin "5") (pinfunction "DIG6_5") (pintype "output"))
    )
    (net (code "47") (name "Net-(U3-DIG7)") (class "Default")
      (node (ref "LED104") (pin "C") (pinfunction "C_C") (pintype "passive"))
      (node (ref "LED72") (pin "C") (pinfunction "C_C") (pintype "passive"))
      (node (ref "LED80") (pin "C") (pinfunction "C_C") (pintype "passive"))
      (node (ref "LED88") (pin "C") (pinfunction "C_C") (pintype "passive"))
      (node (ref "LED96") (pin "C") (pinfunction "C_C") (pintype "passive"))
      (node (ref "U3") (pin "8") (pinfunction "DIG7_8") (pintype "output"))
    )
    (net (code "48") (name "Net-(U3-ISET)") (class "Default")
      (node (ref "R3") (pin "2") (pinfunction "2_2") (pintype "passive"))
      (node (ref "U3") (pin "18") (pinfunction "ISET_18") (pintype "input"))
    )
    (net (code "49") (name "Net-(U3-SEGA)") (class "Default")
      (node (ref "LED65") (pin "A") (pinfunction "A_A") (pintype "passive"))
      (node (ref "LED66") (pin "A") (pinfunction "A_A") (pintype "passive"))
      (node (ref "LED67") (pin "A") (pinfunction "A_A") (pintype "passive"))
      (node (ref "LED68") (pin "A") (pinfunction "A_A") (pintype "passive"))
      (node (ref "LED69") (pin "A") (pinfunction "A_A") (pintype "passive"))
      (node (ref "LED70") (pin "A") (pinfunction "A_A") (pintype "passive"))
      (node (ref "LED71") (pin "A") (pinfunction "A_A") (pintype "passive"))
      (node (ref "LED72") (pin "A") (pinfunction "A_A") (pintype "passive"))
      (node (ref "U3") (pin "14") (pinfunction "SEGA_14") (pintype "output"))
    )
    (net (code "50") (name "Net-(U3-SEGB)") (class "Default")
      (node (ref "LED73") (pin "A") (pinfunction "A_A") (pintype "passive"))
      (node (ref "LED74") (pin "A") (pinfunction "A_A") (pintype "passive"))
      (node (ref "LED75") (pin "A") (pinfunction "A_A") (pintype "passive"))
      (node (ref "LED76") (pin "A") (pinfunction "A_A") (pintype "passive"))
      (node (ref "LED77") (pin "A") (pinfunction "A_A") (pintype "passive"))
      (node (ref "LED78") (pin "A") (pinfunction "A_A") (pintype "passive"))
      (node (ref "LED79") (pin "A") (pinfunction "A_A") (pintype "passive"))
      (node (ref "LED80") (pin "A") (pinfunction "A_A") (pintype "passive"))
      (node (ref "U3") (pin "16") (pinfunction "SEGB_16") (pintype "output"))
    )
    (net (code "51") (name "Net-(U3-SEGC)") (class "Default")
      (node (ref "LED81") (pin "A") (pinfunction "A_A") (pintype "passive"))
      (node (ref "LED82") (pin "A") (pinfunction "A_A") (pintype "passive"))
      (node (ref "LED83") (pin "A") (pinfunction "A_A") (pintype "passive"))
      (node (ref "LED84") (pin "A") (pinfunction "A_A") (pintype "passive"))
      (node (ref "LED85") (pin "A") (pinfunction "A_A") (pintype "passive"))
      (node (ref "LED86") (pin "A") (pinfunction "A_A") (pintype "passive"))
      (node (ref "LED87") (pin "A") (pinfunction "A_A") (pintype "passive"))
      (node (ref "LED88") (pin "A") (pinfunction "A_A") (pintype "passive"))
      (node (ref "U3") (pin "20") (pinfunction "SEGC_20") (pintype "output"))
    )
    (net (code "52") (name "Net-(U3-SEGD)") (class "Default")
      (node (ref "LED89") (pin "A") (pinfunction "A_A") (pintype "passive"))
      (node (ref "LED90") (pin "A") (pinfunction "A_A") (pintype "passive"))
      (node (ref "LED91") (pin "A") (pinfunction "A_A") (pintype "passive"))
      (node (ref "LED92") (pin "A") (pinfunction "A_A") (pintype "passive"))
      (node (ref "LED93") (pin "A") (pinfunction "A_A") (pintype "passive"))
      (node (ref "LED94") (pin "A") (pinfunction "A_A") (pintype "passive"))
      (node (ref "LED95") (pin "A") (pinfunction "A_A") (pintype "passive"))
      (node (ref "LED96") (pin "A") (pinfunction "A_A") (pintype "passive"))
      (node (ref "U3") (pin "23") (pinfunction "SEGD_23") (pintype "output"))
    )
    (net (code "53") (name "Net-(U3-SEGE)") (class "Default")
      (node (ref "LED100") (pin "A") (pinfunction "A_A") (pintype "passive"))
      (node (ref "LED101") (pin "A") (pinfunction "A_A") (pintype "passive"))
      (node (ref "LED102") (pin "A") (pinfunction "A_A") (pintype "passive"))
      (node (ref "LED103") (pin "A") (pinfunction "A_A") (pintype "passive"))
      (node (ref "LED104") (pin "A") (pinfunction "A_A") (pintype "passive"))
      (node (ref "LED97") (pin "A") (pinfunction "A_A") (pintype "passive"))
      (node (ref "LED98") (pin "A") (pinfunction "A_A") (pintype "passive"))
      (node (ref "LED99") (pin "A") (pinfunction "A_A") (pintype "passive"))
      (node (ref "U3") (pin "21") (pinfunction "SEGE_21") (pintype "output"))
    )
    (net (code "54") (name "Net-(U3-SEGF)") (class "Default")
      (node (ref "LED105") (pin "A") (pinfunction "A_A") (pintype "passive"))
      (node (ref "LED106") (pin "A") (pinfunction "A_A") (pintype "passive"))
      (node (ref "LED107") (pin "A") (pinfunction "A_A") (pintype "passive"))
      (node (ref "LED108") (pin "A") (pinfunction "A_A") (pintype "passive"))
      (node (ref "LED109") (pin "A") (pinfunction "A_A") (pintype "passive"))
      (node (ref "LED110") (pin "A") (pinfunction "A_A") (pintype "passive"))
      (node (ref "U3") (pin "15") (pinfunction "SEGF_15") (pintype "output"))
    )
    (net (code "55") (name "RST") (class "Default")
      (node (ref "C8") (pin "1") (pinfunction "1_1") (pintype "passive"))
      (node (ref "MDL1") (pin "1") (pinfunction "REST_1") (pintype "bidirectional"))
      (node (ref "R5") (pin "1") (pinfunction "1_1") (pintype "passive"))
      (node (ref "T1") (pin "C") (pinfunction "C_C") (pintype "passive"))
    )
    (net (code "56") (name "RXD") (class "Default")
      (node (ref "JP3") (pin "6") (pinfunction "6_6") (pintype "passive"))
      (node (ref "MDL1") (pin "15") (pinfunction "RXD_15") (pintype "bidirectional"))
    )
    (net (code "57") (name "SCL") (class "Default")
      (node (ref "MDL1") (pin "14") (pinfunction "GPIO5_14") (pintype "bidirectional"))
      (node (ref "U$3") (pin "SCL") (pinfunction "SCL_SCL") (pintype "bidirectional"))
    )
    (net (code "58") (name "SDA") (class "Default")
      (node (ref "MDL1") (pin "13") (pinfunction "GPIO4_13") (pintype "bidirectional"))
      (node (ref "U$3") (pin "SDA") (pinfunction "SDA_SDA") (pintype "bidirectional"))
    )
    (net (code "59") (name "TXD") (class "Default")
      (node (ref "JP3") (pin "7") (pinfunction "7_7") (pintype "passive"))
      (node (ref "MDL1") (pin "16") (pinfunction "TXD_16") (pintype "bidirectional"))
    )
    (net (code "60") (name "unconnected-(MDL1-ADC-Pad2)") (class "Default")
      (node (ref "MDL1") (pin "2") (pinfunction "ADC_2") (pintype "bidirectional"))
    )
    (net (code "61") (name "unconnected-(MDL1-CS0-Pad17)") (class "Default")
      (node (ref "MDL1") (pin "17") (pinfunction "CS0_17") (pintype "bidirectional"))
    )
    (net (code "62") (name "unconnected-(MDL1-GPIO9-Pad19)") (class "Default")
      (node (ref "MDL1") (pin "19") (pinfunction "GPIO9_19") (pintype "bidirectional"))
    )
    (net (code "63") (name "unconnected-(MDL1-GPIO10-Pad20)") (class "Default")
      (node (ref "MDL1") (pin "20") (pinfunction "GPIO10_20") (pintype "bidirectional"))
    )
    (net (code "64") (name "unconnected-(MDL1-MISO-Pad18)") (class "Default")
      (node (ref "MDL1") (pin "18") (pinfunction "MISO_18") (pintype "bidirectional"))
    )
    (net (code "65") (name "unconnected-(MDL1-MOSI-Pad21)") (class "Default")
      (node (ref "MDL1") (pin "21") (pinfunction "MOSI_21") (pintype "bidirectional"))
    )
    (net (code "66") (name "unconnected-(MDL1-SCLK-Pad22)") (class "Default")
      (node (ref "MDL1") (pin "22") (pinfunction "SCLK_22") (pintype "bidirectional"))
    )
    (net (code "67") (name "unconnected-(U$3-DS-PadDS@2)") (class "Default")
      (node (ref "U$3") (pin "DS@2") (pinfunction "DS_DS@2") (pintype "bidirectional"))
    )
    (net (code "68") (name "unconnected-(U$3-GND-PadGND@2)") (class "Default")
      (node (ref "U$3") (pin "GND@2") (pinfunction "GND_GND@2") (pintype "bidirectional"))
    )
    (net (code "69") (name "unconnected-(U$3-PadBAT)") (class "Default")
      (node (ref "U$3") (pin "BAT") (pinfunction "BAT_BAT") (pintype "bidirectional"))
    )
    (net (code "70") (name "unconnected-(U$3-PadDS)") (class "Default")
      (node (ref "U$3") (pin "DS") (pinfunction "DS_DS") (pintype "bidirectional"))
    )
    (net (code "71") (name "unconnected-(U$3-PadSQ)") (class "Default")
      (node (ref "U$3") (pin "SQ") (pinfunction "SQ_SQ") (pintype "bidirectional"))
    )
    (net (code "72") (name "unconnected-(U$3-SCL-PadSCL@2)") (class "Default")
      (node (ref "U$3") (pin "SCL@2") (pinfunction "SCL_SCL@2") (pintype "bidirectional"))
    )
    (net (code "73") (name "unconnected-(U$3-SDA-PadSDA@2)") (class "Default")
      (node (ref "U$3") (pin "SDA@2") (pinfunction "SDA_SDA@2") (pintype "bidirectional"))
    )
    (net (code "74") (name "unconnected-(U$3-VCC-PadVCC@2)") (class "Default")
      (node (ref "U$3") (pin "VCC@2") (pinfunction "VCC_VCC@2") (pintype "bidirectional"))
    )
    (net (code "75") (name "unconnected-(U2-DOUT-Pad24)") (class "Default")
      (node (ref "U2") (pin "24") (pinfunction "DOUT_24") (pintype "output"))
    )
    (net (code "76") (name "unconnected-(U3-SEGDP-Pad22)") (class "Default")
      (node (ref "U3") (pin "22") (pinfunction "SEGDP_22") (pintype "output"))
    )
    (net (code "77") (name "unconnected-(U3-SEGG-Pad17)") (class "Default")
      (node (ref "U3") (pin "17") (pinfunction "SEGG_17") (pintype "output"))
    )
  )
)
